# shield-no_ps.net
KiCad netlist of a schematic drawn in EAGLE
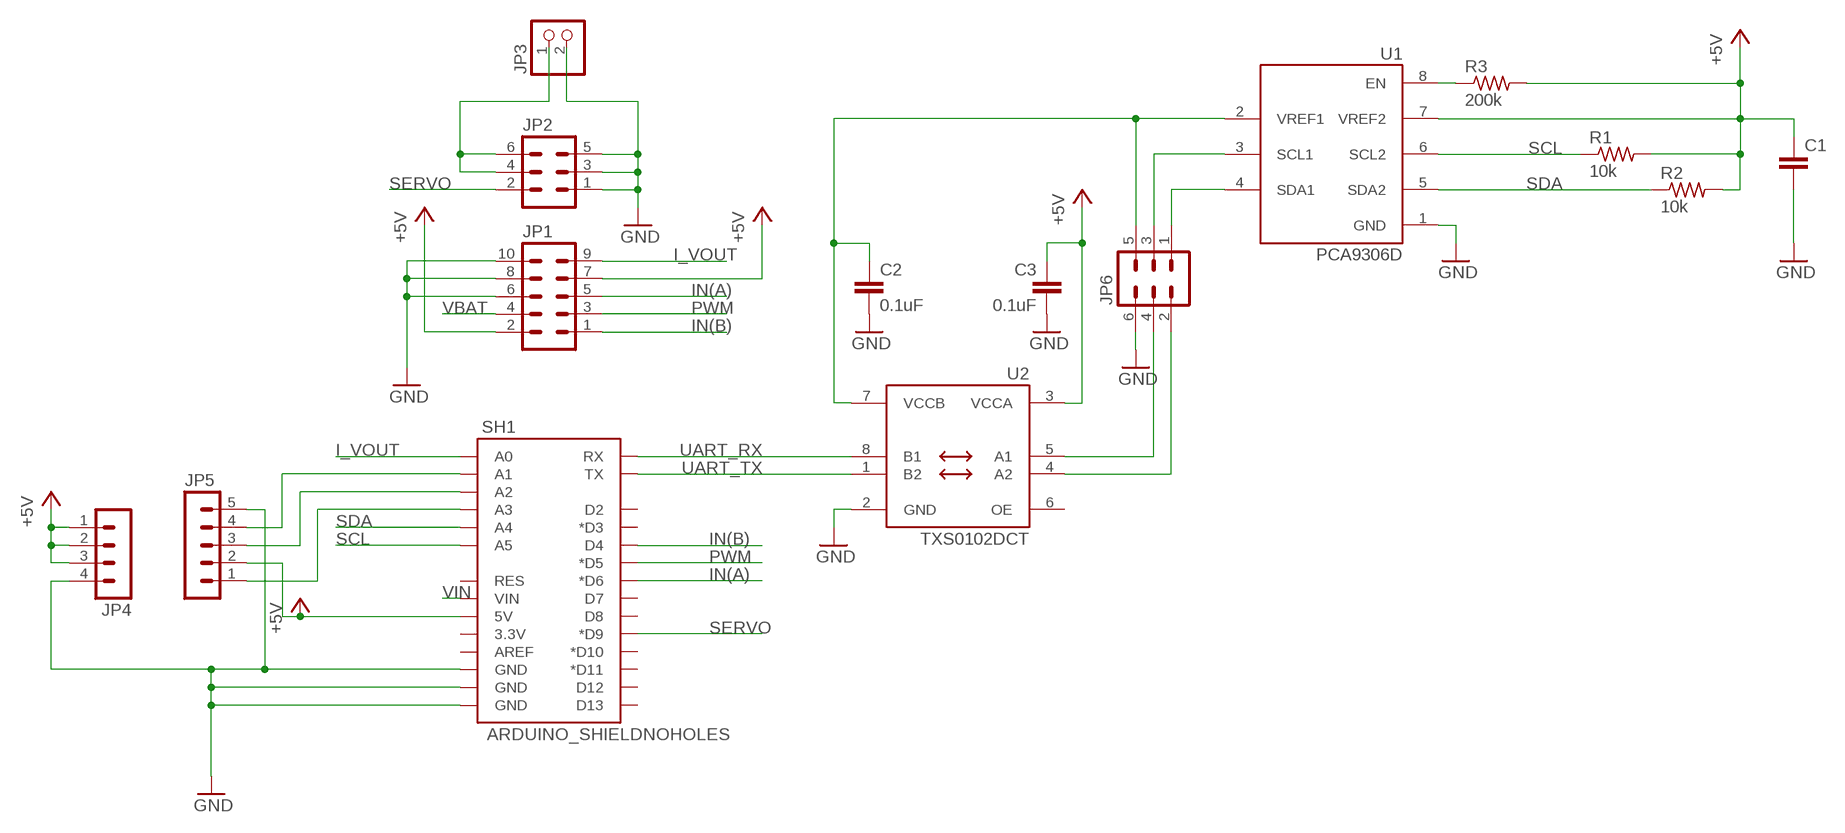
[diagram p0: schematic, sheet 1]

(export (version "E")
  (design (tool "Eeschema 10.0.6"))
  (components
    (comp (ref "C1")
      (value "C-EUC0805")
      (footprint "eagle-import:C0805")
      (libsource (lib "eagle-import") (part "C-EUC0805"))
    )
    (comp (ref "C2")
      (value "0.1uF")
      (footprint "eagle-import:C0603")
      (libsource (lib "eagle-import") (part "C-EUC0603"))
    )
    (comp (ref "C3")
      (value "0.1uF")
      (footprint "eagle-import:C0603")
      (libsource (lib "eagle-import") (part "C-EUC0603"))
    )
    (comp (ref "JP1")
      (value "ML10")
      (footprint "eagle-import:ML10")
      (libsource (lib "eagle-import") (part "ML10"))
    )
    (comp (ref "JP2")
      (value "ML6")
      (footprint "eagle-import:ML6")
      (libsource (lib "eagle-import") (part "ML6"))
    )
    (comp (ref "JP3")
      (value "PINHD-1X2")
      (footprint "eagle-import:1X02")
      (libsource (lib "eagle-import") (part "PINHD-1X2"))
    )
    (comp (ref "JP4")
      (value "MA04-1")
      (footprint "eagle-import:MA04-1")
      (libsource (lib "eagle-import") (part "MA04-1"))
    )
    (comp (ref "JP5")
      (value "MA05-1")
      (footprint "eagle-import:MA05-1")
      (fields (field (name "OC_FARNELL") "unknown") (field (name "OC_NEWARK") "unknown"))
      (libsource (lib "eagle-import") (part "MA05-1"))
    )
    (comp (ref "JP6")
      (value "ML6")
      (footprint "eagle-import:ML6")
      (libsource (lib "eagle-import") (part "ML6"))
    )
    (comp (ref "R1")
      (value "10k")
      (footprint "eagle-import:R0805")
      (libsource (lib "eagle-import") (part "R-US_R0805"))
    )
    (comp (ref "R2")
      (value "10k")
      (footprint "eagle-import:R0805")
      (libsource (lib "eagle-import") (part "R-US_R0805"))
    )
    (comp (ref "R3")
      (value "200k")
      (footprint "eagle-import:R0603")
      (libsource (lib "eagle-import") (part "R-US_R0603"))
    )
    (comp (ref "SH1")
      (value "ARDUINO_SHIELDNOHOLES")
      (footprint "eagle-import:DUEMILANOVE_SHIELD_NOHOLES")
      (libsource (lib "eagle-import") (part "ARDUINO_SHIELDNOHOLES"))
    )
    (comp (ref "U1")
      (value "PCA9306D")
      (footprint "eagle-import:SO8")
      (libsource (lib "eagle-import") (part "PCA9306D"))
    )
    (comp (ref "U2")
      (value "TXS0102DCT")
      (footprint "eagle-import:DCT_R-PDSO-G8")
      (libsource (lib "eagle-import") (part "TXS0102DCT"))
    )
  )
  (nets
    (net (code "1") (name "+5V") (class "Default")
      (node (ref "C1") (pin "1") (pinfunction "1_1") (pintype "passive"))
      (node (ref "C3") (pin "1") (pinfunction "1_1") (pintype "passive"))
      (node (ref "JP1") (pin "2") (pinfunction "2_2") (pintype "passive"))
      (node (ref "JP1") (pin "7") (pinfunction "7_7") (pintype "passive"))
      (node (ref "JP4") (pin "1") (pinfunction "1_1") (pintype "passive"))
      (node (ref "JP4") (pin "2") (pinfunction "2_2") (pintype "passive"))
      (node (ref "JP4") (pin "3") (pinfunction "3_3") (pintype "passive"))
      (node (ref "JP5") (pin "2") (pinfunction "2_2") (pintype "passive"))
      (node (ref "R1") (pin "2") (pinfunction "2_2") (pintype "passive"))
      (node (ref "R2") (pin "2") (pinfunction "2_2") (pintype "passive"))
      (node (ref "R3") (pin "2") (pinfunction "2_2") (pintype "passive"))
      (node (ref "SH1") (pin "5V") (pinfunction "5V_5V") (pintype "bidirectional"))
      (node (ref "U1") (pin "7") (pinfunction "VREF2_7") (pintype "bidirectional"))
      (node (ref "U2") (pin "3") (pinfunction "VCCA_3") (pintype "bidirectional"))
    )
    (net (code "2") (name "/IN(A)") (class "Default")
      (node (ref "JP1") (pin "5") (pinfunction "5_5") (pintype "passive"))
      (node (ref "SH1") (pin "D6") (pinfunction "*D6_D6") (pintype "bidirectional"))
    )
    (net (code "3") (name "/IN(B)") (class "Default")
      (node (ref "JP1") (pin "1") (pinfunction "1_1") (pintype "passive"))
      (node (ref "SH1") (pin "D4") (pinfunction "D4_D4") (pintype "bidirectional"))
    )
    (net (code "4") (name "/I_VOUT") (class "Default")
      (node (ref "JP1") (pin "9") (pinfunction "9_9") (pintype "passive"))
      (node (ref "SH1") (pin "A0") (pinfunction "A0_A0") (pintype "bidirectional"))
    )
    (net (code "5") (name "/PWM") (class "Default")
      (node (ref "JP1") (pin "3") (pinfunction "3_3") (pintype "passive"))
      (node (ref "SH1") (pin "D5") (pinfunction "*D5_D5") (pintype "bidirectional"))
    )
    (net (code "6") (name "/SCL") (class "Default")
      (node (ref "R1") (pin "1") (pinfunction "1_1") (pintype "passive"))
      (node (ref "SH1") (pin "A5") (pinfunction "A5_A5") (pintype "bidirectional"))
      (node (ref "U1") (pin "6") (pinfunction "SCL2_6") (pintype "bidirectional"))
    )
    (net (code "7") (name "/SDA") (class "Default")
      (node (ref "R2") (pin "1") (pinfunction "1_1") (pintype "passive"))
      (node (ref "SH1") (pin "A4") (pinfunction "A4_A4") (pintype "bidirectional"))
      (node (ref "U1") (pin "5") (pinfunction "SDA2_5") (pintype "bidirectional"))
    )
    (net (code "8") (name "/SERVO") (class "Default")
      (node (ref "JP2") (pin "2") (pinfunction "2_2") (pintype "passive"))
      (node (ref "SH1") (pin "D9") (pinfunction "*D9_D9") (pintype "bidirectional"))
    )
    (net (code "9") (name "/UART_RX") (class "Default")
      (node (ref "SH1") (pin "RX") (pinfunction "RX_RX") (pintype "bidirectional"))
      (node (ref "U2") (pin "8") (pinfunction "B1_8") (pintype "bidirectional"))
    )
    (net (code "10") (name "/UART_TX") (class "Default")
      (node (ref "SH1") (pin "TX") (pinfunction "TX_TX") (pintype "bidirectional"))
      (node (ref "U2") (pin "1") (pinfunction "B2_1") (pintype "bidirectional"))
    )
    (net (code "11") (name "/VBAT") (class "Default")
      (node (ref "JP1") (pin "4") (pinfunction "4_4") (pintype "passive"))
    )
    (net (code "12") (name "/VIN") (class "Default")
      (node (ref "SH1") (pin "VIN") (pinfunction "VIN_VIN") (pintype "bidirectional"))
    )
    (net (code "13") (name "GND") (class "Default")
      (node (ref "C1") (pin "2") (pinfunction "2_2") (pintype "passive"))
      (node (ref "C2") (pin "2") (pinfunction "2_2") (pintype "passive"))
      (node (ref "C3") (pin "2") (pinfunction "2_2") (pintype "passive"))
      (node (ref "JP1") (pin "10") (pinfunction "10_10") (pintype "passive"))
      (node (ref "JP1") (pin "6") (pinfunction "6_6") (pintype "passive"))
      (node (ref "JP1") (pin "8") (pinfunction "8_8") (pintype "passive"))
      (node (ref "JP2") (pin "1") (pinfunction "1_1") (pintype "passive"))
      (node (ref "JP2") (pin "3") (pinfunction "3_3") (pintype "passive"))
      (node (ref "JP2") (pin "5") (pinfunction "5_5") (pintype "passive"))
      (node (ref "JP3") (pin "2") (pinfunction "2_2") (pintype "passive"))
      (node (ref "JP4") (pin "4") (pinfunction "4_4") (pintype "passive"))
      (node (ref "JP5") (pin "5") (pinfunction "5_5") (pintype "passive"))
      (node (ref "JP6") (pin "6") (pinfunction "6_6") (pintype "passive"))
      (node (ref "SH1") (pin "GND@0") (pinfunction "GND_GND@0") (pintype "bidirectional"))
      (node (ref "SH1") (pin "GND@1") (pinfunction "GND_GND@1") (pintype "bidirectional"))
      (node (ref "SH1") (pin "GND@2") (pinfunction "GND_GND@2") (pintype "bidirectional"))
      (node (ref "U1") (pin "1") (pinfunction "GND_1") (pintype "bidirectional"))
      (node (ref "U2") (pin "2") (pinfunction "GND_2") (pintype "bidirectional"))
    )
    (net (code "14") (name "Net-(JP2-Pad4)") (class "Default")
      (node (ref "JP2") (pin "4") (pinfunction "4_4") (pintype "passive"))
      (node (ref "JP2") (pin "6") (pinfunction "6_6") (pintype "passive"))
      (node (ref "JP3") (pin "1") (pinfunction "1_1") (pintype "passive"))
    )
    (net (code "15") (name "Net-(JP5-Pad1)") (class "Default")
      (node (ref "JP5") (pin "1") (pinfunction "1_1") (pintype "passive"))
      (node (ref "SH1") (pin "A3") (pinfunction "A3_A3") (pintype "bidirectional"))
    )
    (net (code "16") (name "Net-(JP5-Pad3)") (class "Default")
      (node (ref "JP5") (pin "3") (pinfunction "3_3") (pintype "passive"))
      (node (ref "SH1") (pin "A2") (pinfunction "A2_A2") (pintype "bidirectional"))
    )
    (net (code "17") (name "Net-(JP5-Pad4)") (class "Default")
      (node (ref "JP5") (pin "4") (pinfunction "4_4") (pintype "passive"))
      (node (ref "SH1") (pin "A1") (pinfunction "A1_A1") (pintype "bidirectional"))
    )
    (net (code "18") (name "Net-(U1-EN)") (class "Default")
      (node (ref "R3") (pin "1") (pinfunction "1_1") (pintype "passive"))
      (node (ref "U1") (pin "8") (pinfunction "EN_8") (pintype "bidirectional"))
    )
    (net (code "19") (name "Net-(U1-SCL1)") (class "Default")
      (node (ref "JP6") (pin "3") (pinfunction "3_3") (pintype "passive"))
      (node (ref "U1") (pin "3") (pinfunction "SCL1_3") (pintype "bidirectional"))
    )
    (net (code "20") (name "Net-(U1-SDA1)") (class "Default")
      (node (ref "JP6") (pin "1") (pinfunction "1_1") (pintype "passive"))
      (node (ref "U1") (pin "4") (pinfunction "SDA1_4") (pintype "bidirectional"))
    )
    (net (code "21") (name "Net-(U1-VREF1)") (class "Default")
      (node (ref "C2") (pin "1") (pinfunction "1_1") (pintype "passive"))
      (node (ref "JP6") (pin "5") (pinfunction "5_5") (pintype "passive"))
      (node (ref "U1") (pin "2") (pinfunction "VREF1_2") (pintype "bidirectional"))
      (node (ref "U2") (pin "7") (pinfunction "VCCB_7") (pintype "bidirectional"))
    )
    (net (code "22") (name "Net-(U2-A1)") (class "Default")
      (node (ref "JP6") (pin "4") (pinfunction "4_4") (pintype "passive"))
      (node (ref "U2") (pin "5") (pinfunction "A1_5") (pintype "bidirectional"))
    )
    (net (code "23") (name "Net-(U2-A2)") (class "Default")
      (node (ref "JP6") (pin "2") (pinfunction "2_2") (pintype "passive"))
      (node (ref "U2") (pin "4") (pinfunction "A2_4") (pintype "bidirectional"))
    )
    (net (code "24") (name "unconnected-(SH1-*D3-PadD3)") (class "Default")
      (node (ref "SH1") (pin "D3") (pinfunction "*D3_D3") (pintype "bidirectional"))
    )
    (net (code "25") (name "unconnected-(SH1-*D10-PadD10)") (class "Default")
      (node (ref "SH1") (pin "D10") (pinfunction "*D10_D10") (pintype "bidirectional"))
    )
    (net (code "26") (name "unconnected-(SH1-*D11-PadD11)") (class "Default")
      (node (ref "SH1") (pin "D11") (pinfunction "*D11_D11") (pintype "bidirectional"))
    )
    (net (code "27") (name "unconnected-(SH1-Pad3.3V)") (class "Default")
      (node (ref "SH1") (pin "3.3V") (pinfunction "3.3V_3.3V") (pintype "bidirectional"))
    )
    (net (code "28") (name "unconnected-(SH1-PadAREF)") (class "Default")
      (node (ref "SH1") (pin "AREF") (pinfunction "AREF_AREF") (pintype "bidirectional"))
    )
    (net (code "29") (name "unconnected-(SH1-PadD2)") (class "Default")
      (node (ref "SH1") (pin "D2") (pinfunction "D2_D2") (pintype "bidirectional"))
    )
    (net (code "30") (name "unconnected-(SH1-PadD7)") (class "Default")
      (node (ref "SH1") (pin "D7") (pinfunction "D7_D7") (pintype "bidirectional"))
    )
    (net (code "31") (name "unconnected-(SH1-PadD8)") (class "Default")
      (node (ref "SH1") (pin "D8") (pinfunction "D8_D8") (pintype "bidirectional"))
    )
    (net (code "32") (name "unconnected-(SH1-PadD12)") (class "Default")
      (node (ref "SH1") (pin "D12") (pinfunction "D12_D12") (pintype "bidirectional"))
    )
    (net (code "33") (name "unconnected-(SH1-PadD13)") (class "Default")
      (node (ref "SH1") (pin "D13") (pinfunction "D13_D13") (pintype "bidirectional"))
    )
    (net (code "34") (name "unconnected-(SH1-PadRES)") (class "Default")
      (node (ref "SH1") (pin "RES") (pinfunction "RES_RES") (pintype "bidirectional"))
    )
    (net (code "35") (name "unconnected-(U2-OE-Pad6)") (class "Default")
      (node (ref "U2") (pin "6") (pinfunction "OE_6") (pintype "bidirectional"))
    )
  )
)
